# IO_Module.net
KiCad netlist of a schematic drawn in EAGLE
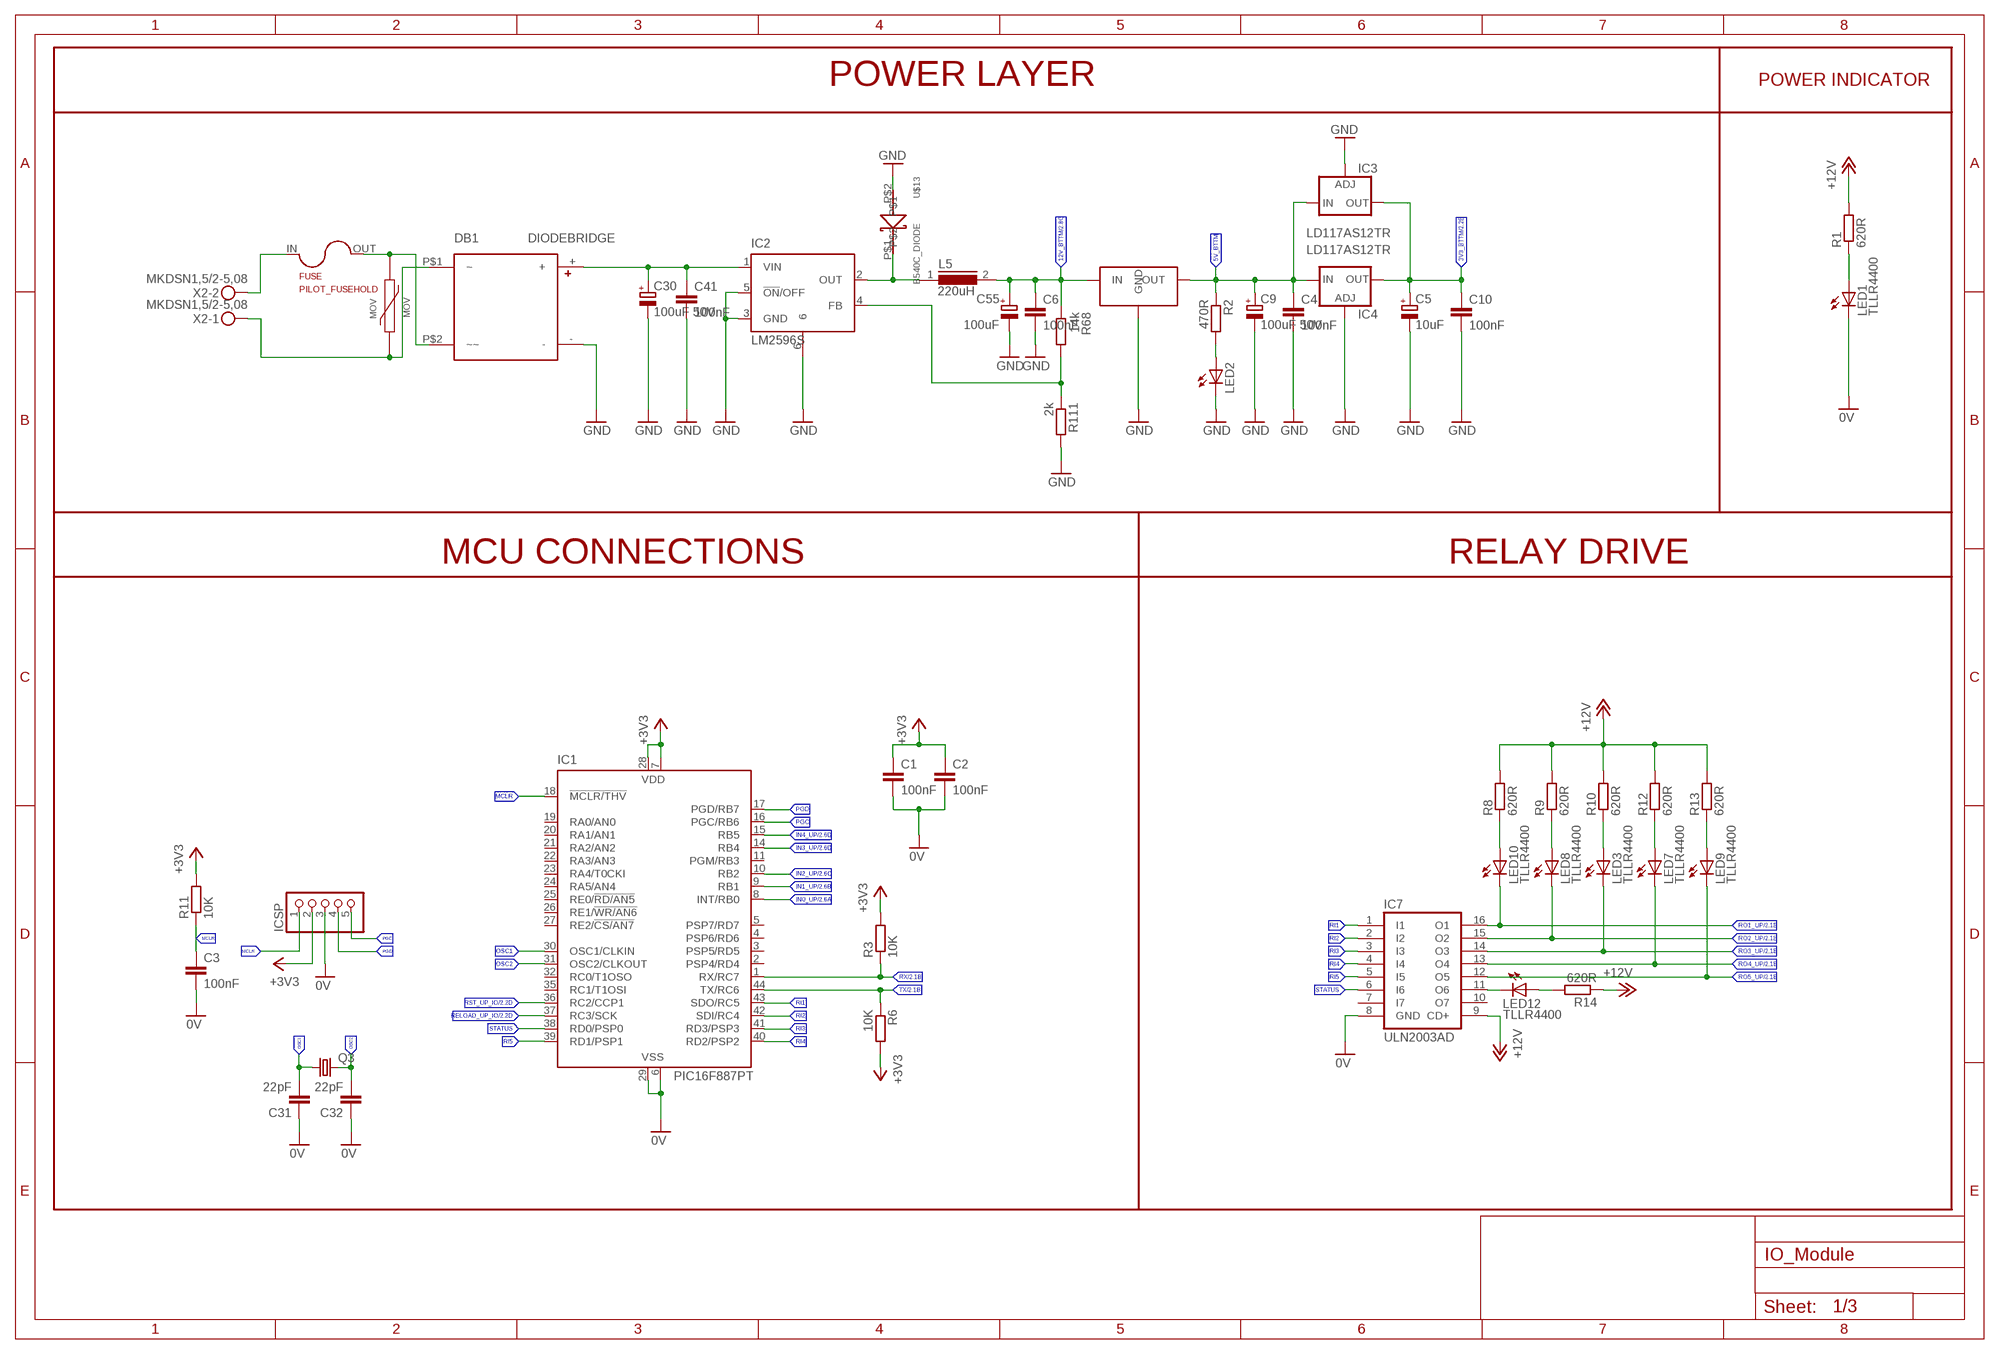
[diagram p0: schematic, sheet 1]
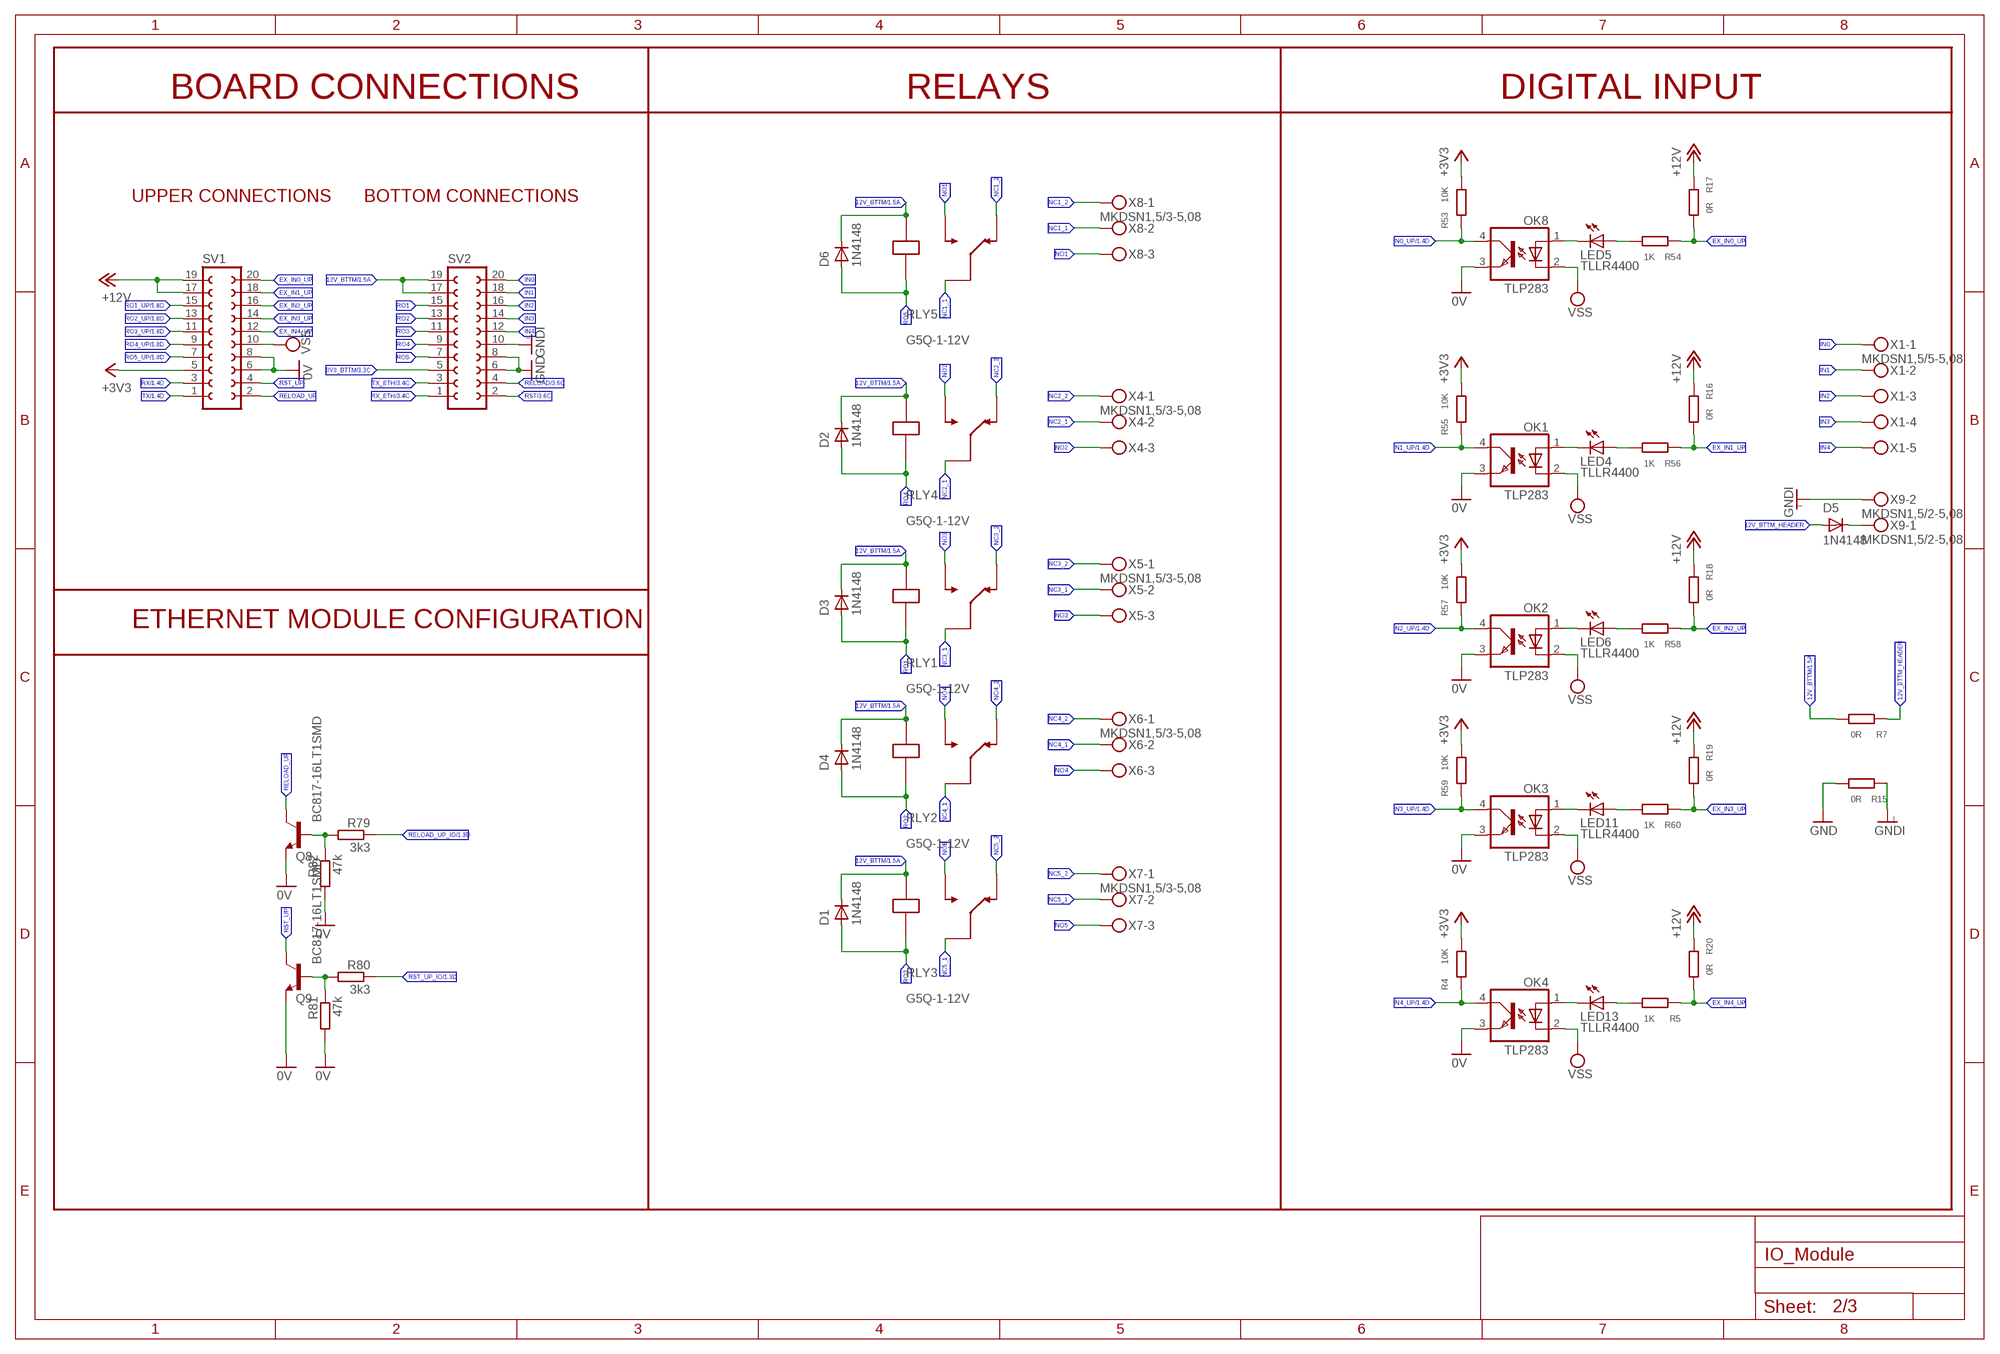
[diagram p1: schematic, sheet 2]
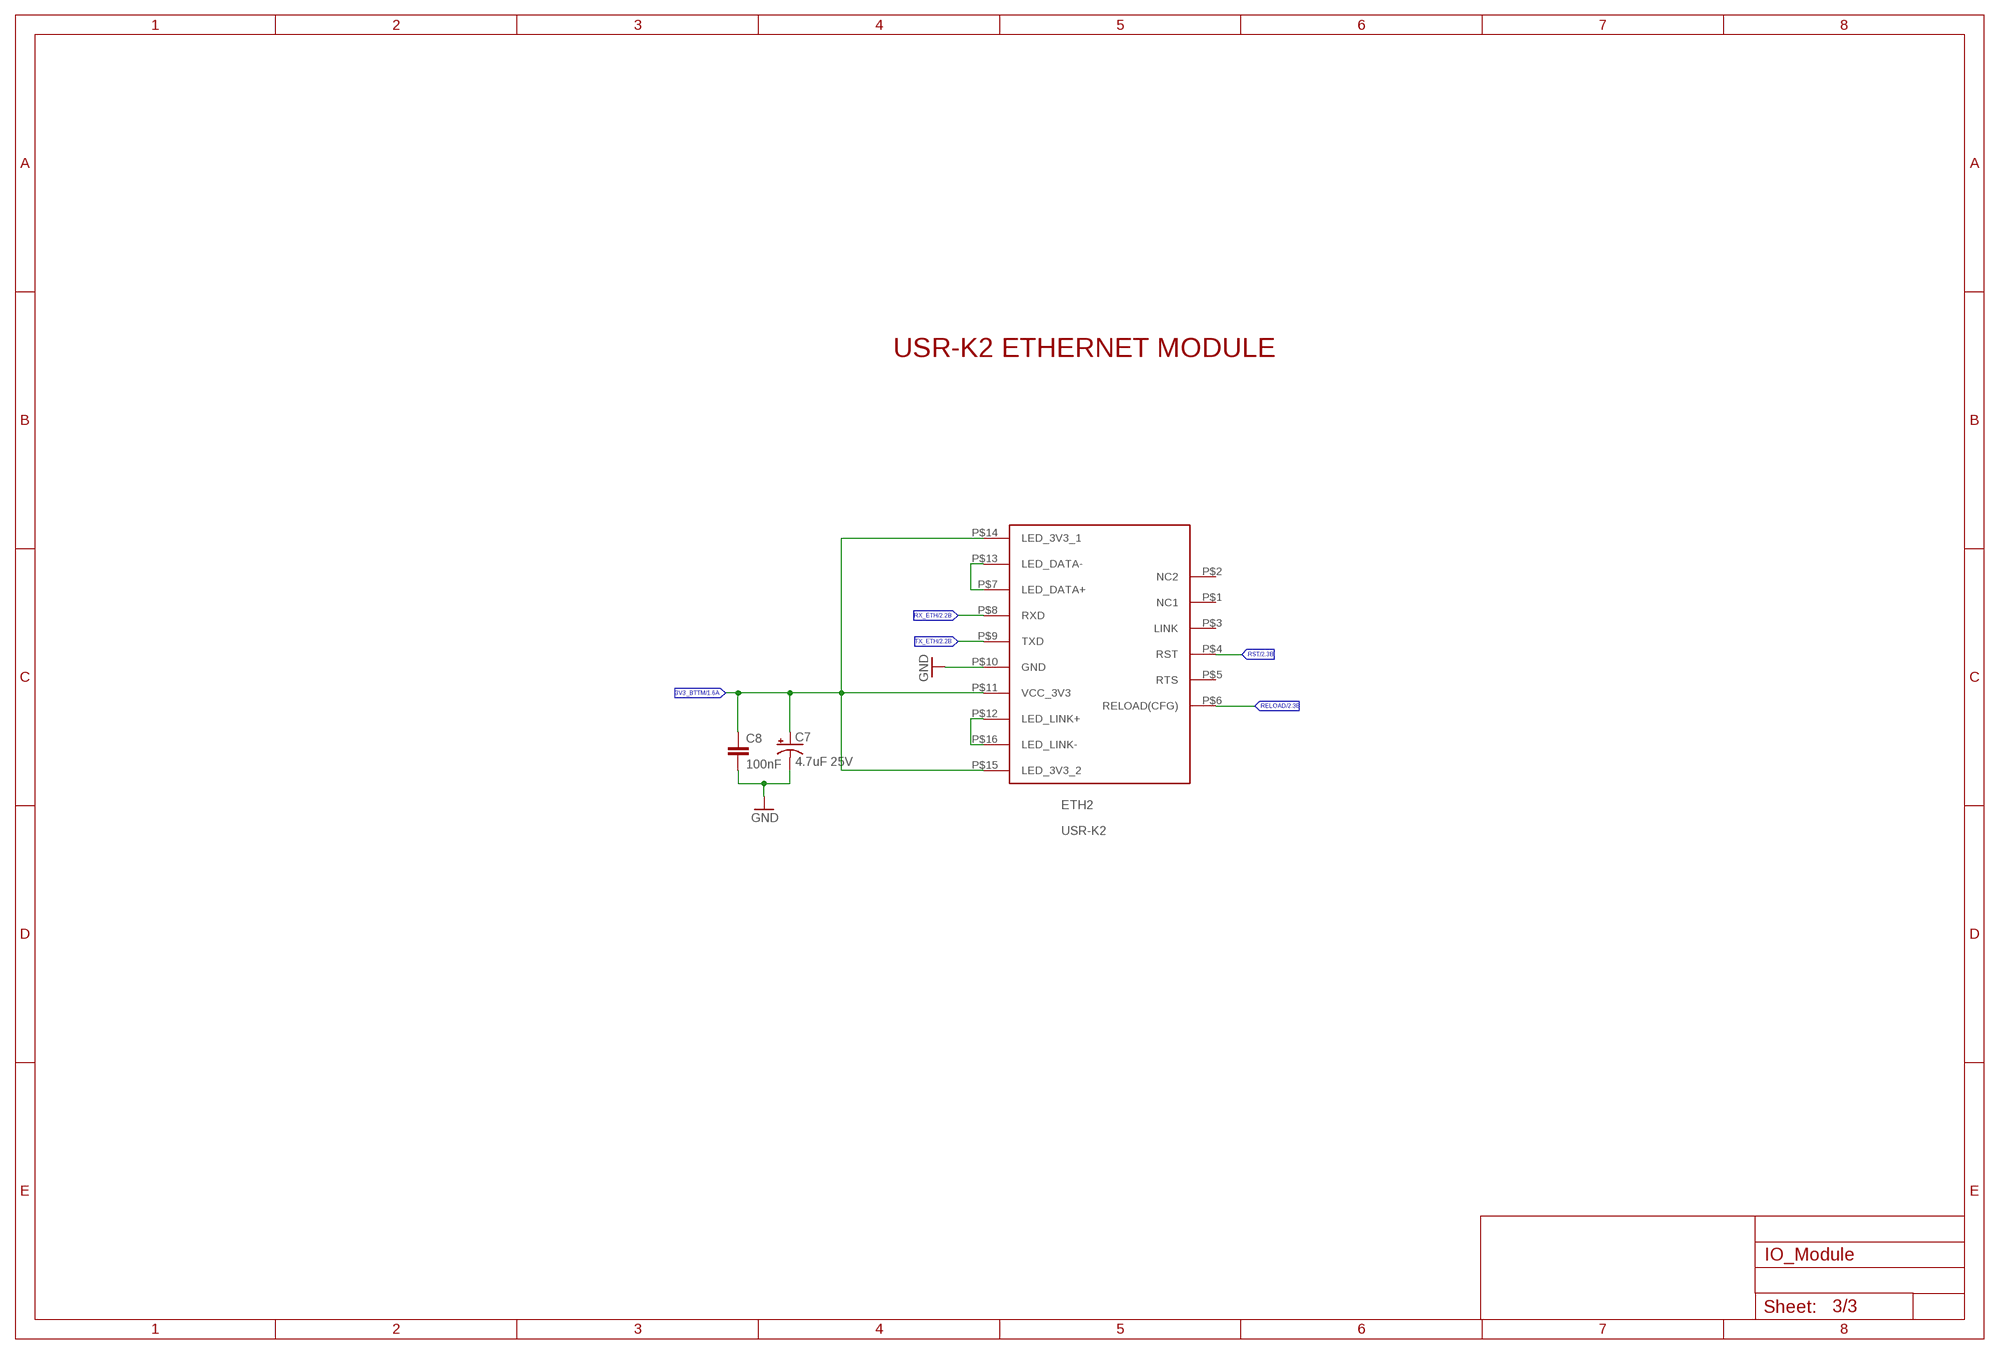
[diagram p2: schematic, sheet 3]

(export (version "E")
  (design (tool "Eeschema 10.0.6"))
  (components
    (comp (ref "C1")
      (value "100nF")
      (footprint "eagle-import:C0603K")
      (libsource (lib "eagle-import") (part "C-EUC0603K"))
    )
    (comp (ref "C2")
      (value "100nF")
      (footprint "eagle-import:C0603K")
      (libsource (lib "eagle-import") (part "C-EUC0603K"))
    )
    (comp (ref "C3")
      (value "100nF")
      (footprint "eagle-import:C0603K")
      (libsource (lib "eagle-import") (part "C-EUC0603K"))
    )
    (comp (ref "C4")
      (value "100nF")
      (footprint "eagle-import:C0603")
      (libsource (lib "eagle-import") (part "C-EUC0603"))
    )
    (comp (ref "C5")
      (value "10uF")
      (footprint "eagle-import:153CLV-0505")
      (libsource (lib "eagle-import") (part "CPOL-EU153CLV-0505"))
    )
    (comp (ref "C6")
      (value "100nF")
      (footprint "eagle-import:C0603")
      (libsource (lib "eagle-import") (part "C-EUC0603"))
    )
    (comp (ref "C9")
      (value "100uF 50V")
      (footprint "eagle-import:153CLV-0810")
      (libsource (lib "eagle-import") (part "CPOL-EU153CLV-0810"))
    )
    (comp (ref "C10")
      (value "100nF")
      (footprint "eagle-import:C0603")
      (libsource (lib "eagle-import") (part "C-EUC0603"))
    )
    (comp (ref "C30")
      (value "100uF 50V")
      (footprint "eagle-import:153CLV-0810")
      (libsource (lib "eagle-import") (part "CPOL-EU153CLV-0810"))
    )
    (comp (ref "C31")
      (value "22pF")
      (footprint "eagle-import:C0805")
      (libsource (lib "eagle-import") (part "C-EUC0805"))
    )
    (comp (ref "C32")
      (value "22pF")
      (footprint "eagle-import:C0805")
      (libsource (lib "eagle-import") (part "C-EUC0805"))
    )
    (comp (ref "C41")
      (value "100nF")
      (footprint "eagle-import:C0603")
      (libsource (lib "eagle-import") (part "C-EUC0603"))
    )
    (comp (ref "C55")
      (value "100uF")
      (footprint "eagle-import:153CLV-0605")
      (libsource (lib "eagle-import") (part "CPOL-EU153CLV-0605"))
    )
    (comp (ref "DB1")
      (value "DIODEBRIDGE")
      (footprint "eagle-import:SDIP")
      (libsource (lib "eagle-import") (part "DIODEBRIDGE"))
    )
    (comp (ref "FUSE")
      (value "PILOT_FUSEHOLD")
      (footprint "eagle-import:RTM_FUSEHOLD")
      (libsource (lib "eagle-import") (part "RTM_FUSEHOLD"))
    )
    (comp (ref "IC1")
      (value "PIC16F887PT")
      (footprint "eagle-import:TQFP44")
      (fields (field (name "MF") "MICROCHIP") (field (name "MPN") "PIC16F877-04/PQ"))
      (libsource (lib "eagle-import") (part "PIC16F87PT7"))
    )
    (comp (ref "IC2")
      (value "LM2596S")
      (footprint "eagle-import:TO263-5")
      (fields (field (name "MF") "NATIONAL SEMICONDUCTOR") (field (name "MPN") "LM2596S-ADJ/NOPB"))
      (libsource (lib "eagle-import") (part "LM2596S"))
    )
    (comp (ref "IC3")
      (value "LD117AS12TR")
      (footprint "eagle-import:SOT223")
      (libsource (lib "eagle-import") (part "LD117A?S12TR"))
    )
    (comp (ref "IC4")
      (value "LD117AS12TR")
      (footprint "eagle-import:SOT223")
      (libsource (lib "eagle-import") (part "LD117A?S12TR"))
    )
    (comp (ref "IC7")
      (value "ULN2003AD")
      (footprint "eagle-import:SO16")
      (libsource (lib "eagle-import") (part "ULN2003AD"))
    )
    (comp (ref "ICSP")
      (value "PINHD-1X5")
      (footprint "eagle-import:1X05")
      (libsource (lib "eagle-import") (part "PINHD-1X5"))
    )
    (comp (ref "L5")
      (value "220uH")
      (footprint "eagle-import:DR125")
      (libsource (lib "eagle-import") (part "DR125"))
    )
    (comp (ref "LED1")
      (value "TLLR4400")
      (footprint "eagle-import:LED3MM")
      (fields (field (name "MF") "VISHAY SEMICONDUCTOR"))
      (libsource (lib "eagle-import") (part "TLLR4400"))
    )
    (comp (ref "LED2")
      (value "LEDCHIPLED_0805")
      (footprint "eagle-import:CHIPLED_0805")
      (libsource (lib "eagle-import") (part "LEDCHIPLED_0805"))
    )
    (comp (ref "LED3")
      (value "TLLR4400")
      (footprint "eagle-import:LED3MM")
      (fields (field (name "MF") "VISHAY SEMICONDUCTOR"))
      (libsource (lib "eagle-import") (part "TLLR4400"))
    )
    (comp (ref "LED7")
      (value "TLLR4400")
      (footprint "eagle-import:LED3MM")
      (fields (field (name "MF") "VISHAY SEMICONDUCTOR"))
      (libsource (lib "eagle-import") (part "TLLR4400"))
    )
    (comp (ref "LED8")
      (value "TLLR4400")
      (footprint "eagle-import:LED3MM")
      (fields (field (name "MF") "VISHAY SEMICONDUCTOR"))
      (libsource (lib "eagle-import") (part "TLLR4400"))
    )
    (comp (ref "LED9")
      (value "TLLR4400")
      (footprint "eagle-import:LED3MM")
      (fields (field (name "MF") "VISHAY SEMICONDUCTOR"))
      (libsource (lib "eagle-import") (part "TLLR4400"))
    )
    (comp (ref "LED10")
      (value "TLLR4400")
      (footprint "eagle-import:LED3MM")
      (fields (field (name "MF") "VISHAY SEMICONDUCTOR"))
      (libsource (lib "eagle-import") (part "TLLR4400"))
    )
    (comp (ref "LED12")
      (value "TLLR4400")
      (footprint "eagle-import:LED3MM")
      (fields (field (name "MF") "VISHAY SEMICONDUCTOR"))
      (libsource (lib "eagle-import") (part "TLLR4400"))
    )
    (comp (ref "MOV")
      (value "MOV-10D201K")
      (footprint "eagle-import:MOV-10D201K")
      (libsource (lib "eagle-import") (part "MOV-10D201K"))
    )
    (comp (ref "Q3")
      (value "CRYSTALHC49UP")
      (footprint "eagle-import:HC49UP")
      (libsource (lib "eagle-import") (part "CRYSTALHC49UP"))
    )
    (comp (ref "R1")
      (value "620R")
      (footprint "eagle-import:R0805")
      (libsource (lib "eagle-import") (part "R-EU_R0805"))
    )
    (comp (ref "R2")
      (value "470R")
      (footprint "eagle-import:R0805")
      (libsource (lib "eagle-import") (part "R-EU_R0805"))
    )
    (comp (ref "R3")
      (value "10K")
      (footprint "eagle-import:R0805")
      (libsource (lib "eagle-import") (part "R-EU_R0805"))
    )
    (comp (ref "R6")
      (value "10K")
      (footprint "eagle-import:R0805")
      (libsource (lib "eagle-import") (part "R-EU_R0805"))
    )
    (comp (ref "R8")
      (value "620R")
      (footprint "eagle-import:R0805")
      (libsource (lib "eagle-import") (part "R-EU_R0805"))
    )
    (comp (ref "R9")
      (value "620R")
      (footprint "eagle-import:R0805")
      (libsource (lib "eagle-import") (part "R-EU_R0805"))
    )
    (comp (ref "R10")
      (value "620R")
      (footprint "eagle-import:R0805")
      (libsource (lib "eagle-import") (part "R-EU_R0805"))
    )
    (comp (ref "R11")
      (value "10K")
      (footprint "eagle-import:R0805")
      (libsource (lib "eagle-import") (part "R-EU_R0805"))
    )
    (comp (ref "R12")
      (value "620R")
      (footprint "eagle-import:R0805")
      (libsource (lib "eagle-import") (part "R-EU_R0805"))
    )
    (comp (ref "R13")
      (value "620R")
      (footprint "eagle-import:R0805")
      (libsource (lib "eagle-import") (part "R-EU_R0805"))
    )
    (comp (ref "R14")
      (value "620R")
      (footprint "eagle-import:R0805")
      (libsource (lib "eagle-import") (part "R-EU_R0805"))
    )
    (comp (ref "R68")
      (value "14k")
      (footprint "eagle-import:M0805")
      (libsource (lib "eagle-import") (part "R-EU_M0805"))
    )
    (comp (ref "R111")
      (value "2k")
      (footprint "eagle-import:M0805")
      (libsource (lib "eagle-import") (part "R-EU_M0805"))
    )
    (comp (ref "U$6")
      (value "L7805CD2T-TR")
      (footprint "eagle-import:VREG-7805-DPAK2")
      (libsource (lib "eagle-import") (part "VREG-7805-DPAK2"))
    )
    (comp (ref "U$13")
      (value "B540C_DIODE")
      (footprint "eagle-import:SMC")
      (libsource (lib "eagle-import") (part "B540C_DIODE"))
    )
    (comp (ref "X2")
      (value "MKDSN1,5/2-5,08")
      (footprint "eagle-import:MKDSN1,5_2-5,08")
      (libsource (lib "eagle-import") (part "MKDSN1,5/2-5,08"))
    )
    (comp (ref "C7")
      (value "4.7uF 25V")
      (footprint "eagle-import:A_3216-18R")
      (libsource (lib "eagle-import") (part "CPOL-USA/3216-18R"))
    )
    (comp (ref "C8")
      (value "100nF")
      (footprint "eagle-import:C0603")
      (libsource (lib "eagle-import") (part "C-EUC0603"))
    )
    (comp (ref "ETH2")
      (value "USR-K2")
      (footprint "eagle-import:USR-K2")
      (libsource (lib "eagle-import") (part "USR-K2"))
    )
    (comp (ref "D1")
      (value "1N4148")
      (footprint "eagle-import:SMA-DO214AC")
      (libsource (lib "eagle-import") (part "GF1"))
    )
    (comp (ref "D2")
      (value "1N4148")
      (footprint "eagle-import:SMA-DO214AC")
      (libsource (lib "eagle-import") (part "GF1"))
    )
    (comp (ref "D3")
      (value "1N4148")
      (footprint "eagle-import:SMA-DO214AC")
      (libsource (lib "eagle-import") (part "GF1"))
    )
    (comp (ref "D4")
      (value "1N4148")
      (footprint "eagle-import:SMA-DO214AC")
      (libsource (lib "eagle-import") (part "GF1"))
    )
    (comp (ref "D5")
      (value "1N4148")
      (footprint "eagle-import:SMA-DO214AC")
      (libsource (lib "eagle-import") (part "GF1"))
    )
    (comp (ref "D6")
      (value "1N4148")
      (footprint "eagle-import:SMA-DO214AC")
      (libsource (lib "eagle-import") (part "GF1"))
    )
    (comp (ref "LED4")
      (value "TLLR4400")
      (footprint "eagle-import:LED3MM")
      (fields (field (name "MF") "VISHAY SEMICONDUCTOR"))
      (libsource (lib "eagle-import") (part "TLLR4400"))
    )
    (comp (ref "LED5")
      (value "TLLR4400")
      (footprint "eagle-import:LED3MM")
      (fields (field (name "MF") "VISHAY SEMICONDUCTOR"))
      (libsource (lib "eagle-import") (part "TLLR4400"))
    )
    (comp (ref "LED6")
      (value "TLLR4400")
      (footprint "eagle-import:LED3MM")
      (fields (field (name "MF") "VISHAY SEMICONDUCTOR"))
      (libsource (lib "eagle-import") (part "TLLR4400"))
    )
    (comp (ref "LED11")
      (value "TLLR4400")
      (footprint "eagle-import:LED3MM")
      (fields (field (name "MF") "VISHAY SEMICONDUCTOR"))
      (libsource (lib "eagle-import") (part "TLLR4400"))
    )
    (comp (ref "LED13")
      (value "TLLR4400")
      (footprint "eagle-import:LED3MM")
      (fields (field (name "MF") "VISHAY SEMICONDUCTOR"))
      (libsource (lib "eagle-import") (part "TLLR4400"))
    )
    (comp (ref "OK1")
      (value "TLP283")
      (footprint "eagle-import:MINI-FLAT-4")
      (libsource (lib "eagle-import") (part "TLP283"))
    )
    (comp (ref "OK2")
      (value "TLP283")
      (footprint "eagle-import:MINI-FLAT-4")
      (libsource (lib "eagle-import") (part "TLP283"))
    )
    (comp (ref "OK3")
      (value "TLP283")
      (footprint "eagle-import:MINI-FLAT-4")
      (libsource (lib "eagle-import") (part "TLP283"))
    )
    (comp (ref "OK4")
      (value "TLP283")
      (footprint "eagle-import:MINI-FLAT-4")
      (libsource (lib "eagle-import") (part "TLP283"))
    )
    (comp (ref "OK8")
      (value "TLP283")
      (footprint "eagle-import:MINI-FLAT-4")
      (libsource (lib "eagle-import") (part "TLP283"))
    )
    (comp (ref "Q8")
      (value "BC817-16LT1SMD")
      (footprint "eagle-import:SOT23-BEC")
      (libsource (lib "eagle-import") (part "BC817SMD-16LT1"))
    )
    (comp (ref "Q9")
      (value "BC817-16LT1SMD")
      (footprint "eagle-import:SOT23-BEC")
      (libsource (lib "eagle-import") (part "BC817SMD-16LT1"))
    )
    (comp (ref "R4")
      (value "10K")
      (footprint "eagle-import:M0805")
      (libsource (lib "eagle-import") (part "R-EU_M0805"))
    )
    (comp (ref "R5")
      (value "1K")
      (footprint "eagle-import:M0805")
      (libsource (lib "eagle-import") (part "R-EU_M0805"))
    )
    (comp (ref "R7")
      (value "0R")
      (footprint "eagle-import:M0805")
      (libsource (lib "eagle-import") (part "R-EU_M0805"))
    )
    (comp (ref "R15")
      (value "0R")
      (footprint "eagle-import:M0805")
      (libsource (lib "eagle-import") (part "R-EU_M0805"))
    )
    (comp (ref "R16")
      (value "0R")
      (footprint "eagle-import:M0805")
      (libsource (lib "eagle-import") (part "R-EU_M0805"))
    )
    (comp (ref "R17")
      (value "0R")
      (footprint "eagle-import:M0805")
      (libsource (lib "eagle-import") (part "R-EU_M0805"))
    )
    (comp (ref "R18")
      (value "0R")
      (footprint "eagle-import:M0805")
      (libsource (lib "eagle-import") (part "R-EU_M0805"))
    )
    (comp (ref "R19")
      (value "0R")
      (footprint "eagle-import:M0805")
      (libsource (lib "eagle-import") (part "R-EU_M0805"))
    )
    (comp (ref "R20")
      (value "0R")
      (footprint "eagle-import:M0805")
      (libsource (lib "eagle-import") (part "R-EU_M0805"))
    )
    (comp (ref "R53")
      (value "10K")
      (footprint "eagle-import:M0805")
      (libsource (lib "eagle-import") (part "R-EU_M0805"))
    )
    (comp (ref "R54")
      (value "1K")
      (footprint "eagle-import:M0805")
      (libsource (lib "eagle-import") (part "R-EU_M0805"))
    )
    (comp (ref "R55")
      (value "10K")
      (footprint "eagle-import:M0805")
      (libsource (lib "eagle-import") (part "R-EU_M0805"))
    )
    (comp (ref "R56")
      (value "1K")
      (footprint "eagle-import:M0805")
      (libsource (lib "eagle-import") (part "R-EU_M0805"))
    )
    (comp (ref "R57")
      (value "10K")
      (footprint "eagle-import:M0805")
      (libsource (lib "eagle-import") (part "R-EU_M0805"))
    )
    (comp (ref "R58")
      (value "1K")
      (footprint "eagle-import:M0805")
      (libsource (lib "eagle-import") (part "R-EU_M0805"))
    )
    (comp (ref "R59")
      (value "10K")
      (footprint "eagle-import:M0805")
      (libsource (lib "eagle-import") (part "R-EU_M0805"))
    )
    (comp (ref "R60")
      (value "1K")
      (footprint "eagle-import:M0805")
      (libsource (lib "eagle-import") (part "R-EU_M0805"))
    )
    (comp (ref "R79")
      (value "3k3")
      (footprint "eagle-import:R0805")
      (libsource (lib "eagle-import") (part "R-EU_R0805"))
    )
    (comp (ref "R80")
      (value "3k3")
      (footprint "eagle-import:R0805")
      (libsource (lib "eagle-import") (part "R-EU_R0805"))
    )
    (comp (ref "R81")
      (value "47k")
      (footprint "eagle-import:R0805")
      (libsource (lib "eagle-import") (part "R-EU_R0805"))
    )
    (comp (ref "R82")
      (value "47k")
      (footprint "eagle-import:R0805")
      (libsource (lib "eagle-import") (part "R-EU_R0805"))
    )
    (comp (ref "RLY1")
      (value "JW1FSN-DC12V")
      (footprint "eagle-import:G5Q-1-12V")
      (libsource (lib "eagle-import") (part "G5Q-1-12V"))
    )
    (comp (ref "RLY2")
      (value "JW1FSN-DC12V")
      (footprint "eagle-import:G5Q-1-12V")
      (libsource (lib "eagle-import") (part "G5Q-1-12V"))
    )
    (comp (ref "RLY3")
      (value "JW1FSN-DC12V")
      (footprint "eagle-import:G5Q-1-12V")
      (libsource (lib "eagle-import") (part "G5Q-1-12V"))
    )
    (comp (ref "RLY4")
      (value "JW1FSN-DC12V")
      (footprint "eagle-import:G5Q-1-12V")
      (libsource (lib "eagle-import") (part "G5Q-1-12V"))
    )
    (comp (ref "RLY5")
      (value "JW1FSN-DC12V")
      (footprint "eagle-import:G5Q-1-12V")
      (libsource (lib "eagle-import") (part "G5Q-1-12V"))
    )
    (comp (ref "SV1")
      (value "FE10-2")
      (footprint "eagle-import:FE10-2")
      (libsource (lib "eagle-import") (part "FE10-2"))
    )
    (comp (ref "SV2")
      (value "FE10-2")
      (footprint "eagle-import:FE10-2")
      (libsource (lib "eagle-import") (part "FE10-2"))
    )
    (comp (ref "X1")
      (value "MKDSN1,5/5-5,08")
      (footprint "eagle-import:MKDSN1,5_5-5,08")
      (libsource (lib "eagle-import") (part "MKDSN1,5/5-5,08"))
    )
    (comp (ref "X4")
      (value "MKDSN1,5/3-5,08")
      (footprint "eagle-import:MKDSN1,5_3-5,08")
      (libsource (lib "eagle-import") (part "MKDSN1,5/3-5,08"))
    )
    (comp (ref "X5")
      (value "MKDSN1,5/3-5,08")
      (footprint "eagle-import:MKDSN1,5_3-5,08")
      (libsource (lib "eagle-import") (part "MKDSN1,5/3-5,08"))
    )
    (comp (ref "X6")
      (value "MKDSN1,5/3-5,08")
      (footprint "eagle-import:MKDSN1,5_3-5,08")
      (libsource (lib "eagle-import") (part "MKDSN1,5/3-5,08"))
    )
    (comp (ref "X7")
      (value "MKDSN1,5/3-5,08")
      (footprint "eagle-import:MKDSN1,5_3-5,08")
      (libsource (lib "eagle-import") (part "MKDSN1,5/3-5,08"))
    )
    (comp (ref "X8")
      (value "MKDSN1,5/3-5,08")
      (footprint "eagle-import:MKDSN1,5_3-5,08")
      (libsource (lib "eagle-import") (part "MKDSN1,5/3-5,08"))
    )
    (comp (ref "X9")
      (value "MKDSN1,5/2-5,08")
      (footprint "eagle-import:MKDSN1,5_2-5,08")
      (libsource (lib "eagle-import") (part "MKDSN1,5/2-5,08"))
    )
  )
  (nets
    (net (code "1") (name "+3V3") (class "Default")
      (node (ref "C1") (pin "1") (pinfunction "1_1") (pintype "passive"))
      (node (ref "C2") (pin "1") (pinfunction "1_1") (pintype "passive"))
      (node (ref "IC1") (pin "28") (pinfunction "VDD_28") (pintype "power_in"))
      (node (ref "IC1") (pin "7") (pinfunction "VDD_7") (pintype "power_in"))
      (node (ref "ICSP") (pin "2") (pinfunction "2_2") (pintype "passive"))
      (node (ref "R11") (pin "2") (pinfunction "2_2") (pintype "passive"))
      (node (ref "R3") (pin "2") (pinfunction "2_2") (pintype "passive"))
      (node (ref "R4") (pin "2") (pinfunction "2_2") (pintype "passive"))
      (node (ref "R53") (pin "2") (pinfunction "2_2") (pintype "passive"))
      (node (ref "R55") (pin "2") (pinfunction "2_2") (pintype "passive"))
      (node (ref "R57") (pin "2") (pinfunction "2_2") (pintype "passive"))
      (node (ref "R59") (pin "2") (pinfunction "2_2") (pintype "passive"))
      (node (ref "R6") (pin "2") (pinfunction "2_2") (pintype "passive"))
      (node (ref "SV1") (pin "5") (pinfunction "5_5") (pintype "passive"))
    )
    (net (code "2") (name "+12V") (class "Default")
      (node (ref "IC7") (pin "9") (pinfunction "CD+_9") (pintype "passive"))
      (node (ref "R1") (pin "2") (pinfunction "2_2") (pintype "passive"))
      (node (ref "R10") (pin "2") (pinfunction "2_2") (pintype "passive"))
      (node (ref "R12") (pin "2") (pinfunction "2_2") (pintype "passive"))
      (node (ref "R13") (pin "2") (pinfunction "2_2") (pintype "passive"))
      (node (ref "R14") (pin "1") (pinfunction "1_1") (pintype "passive"))
      (node (ref "R16") (pin "1") (pinfunction "1_1") (pintype "passive"))
      (node (ref "R17") (pin "1") (pinfunction "1_1") (pintype "passive"))
      (node (ref "R18") (pin "1") (pinfunction "1_1") (pintype "passive"))
      (node (ref "R19") (pin "1") (pinfunction "1_1") (pintype "passive"))
      (node (ref "R20") (pin "1") (pinfunction "1_1") (pintype "passive"))
      (node (ref "R8") (pin "2") (pinfunction "2_2") (pintype "passive"))
      (node (ref "R9") (pin "2") (pinfunction "2_2") (pintype "passive"))
      (node (ref "SV1") (pin "17") (pinfunction "17_17") (pintype "passive"))
      (node (ref "SV1") (pin "19") (pinfunction "19_19") (pintype "passive"))
    )
    (net (code "3") (name "0V") (class "Default")
      (node (ref "C1") (pin "2") (pinfunction "2_2") (pintype "passive"))
      (node (ref "C2") (pin "2") (pinfunction "2_2") (pintype "passive"))
      (node (ref "C3") (pin "2") (pinfunction "2_2") (pintype "passive"))
      (node (ref "C31") (pin "1") (pinfunction "1_1") (pintype "passive"))
      (node (ref "C32") (pin "1") (pinfunction "1_1") (pintype "passive"))
      (node (ref "IC1") (pin "29") (pinfunction "VSS_29") (pintype "power_in"))
      (node (ref "IC1") (pin "6") (pinfunction "VSS_6") (pintype "power_in"))
      (node (ref "IC7") (pin "8") (pinfunction "GND_8") (pintype "power_in"))
      (node (ref "ICSP") (pin "3") (pinfunction "3_3") (pintype "passive"))
      (node (ref "LED1") (pin "K") (pinfunction "C_K") (pintype "passive"))
      (node (ref "OK1") (pin "3") (pinfunction "EMIT_3") (pintype "passive"))
      (node (ref "OK2") (pin "3") (pinfunction "EMIT_3") (pintype "passive"))
      (node (ref "OK3") (pin "3") (pinfunction "EMIT_3") (pintype "passive"))
      (node (ref "OK4") (pin "3") (pinfunction "EMIT_3") (pintype "passive"))
      (node (ref "OK8") (pin "3") (pinfunction "EMIT_3") (pintype "passive"))
      (node (ref "Q8") (pin "E") (pinfunction "E_E") (pintype "passive"))
      (node (ref "Q9") (pin "E") (pinfunction "E_E") (pintype "passive"))
      (node (ref "R81") (pin "2") (pinfunction "2_2") (pintype "passive"))
      (node (ref "R82") (pin "2") (pinfunction "2_2") (pintype "passive"))
      (node (ref "SV1") (pin "6") (pinfunction "6_6") (pintype "passive"))
      (node (ref "SV1") (pin "8") (pinfunction "8_8") (pintype "passive"))
    )
    (net (code "4") (name "3V3_BTTM") (class "Default")
      (node (ref "C10") (pin "1") (pinfunction "1_1") (pintype "passive"))
      (node (ref "C5") (pin "+") (pinfunction "+_+") (pintype "passive"))
      (node (ref "C7") (pin "+") (pinfunction "+_+") (pintype "passive"))
      (node (ref "C8") (pin "1") (pinfunction "1_1") (pintype "passive"))
      (node (ref "ETH2") (pin "P$11") (pinfunction "VCC_3V3_P$11") (pintype "bidirectional"))
      (node (ref "ETH2") (pin "P$14") (pinfunction "LED_3V3_1_P$14") (pintype "bidirectional"))
      (node (ref "ETH2") (pin "P$15") (pinfunction "LED_3V3_2_P$15") (pintype "bidirectional"))
      (node (ref "IC3") (pin "4") (pinfunction "OUT_4") (pintype "passive"))
      (node (ref "IC4") (pin "4") (pinfunction "OUT_4") (pintype "passive"))
      (node (ref "SV2") (pin "5") (pinfunction "5_5") (pintype "passive"))
    )
    (net (code "5") (name "5V_BTTM") (class "Default")
      (node (ref "C4") (pin "1") (pinfunction "1_1") (pintype "passive"))
      (node (ref "C9") (pin "+") (pinfunction "+_+") (pintype "passive"))
      (node (ref "IC3") (pin "3") (pinfunction "IN_3") (pintype "input"))
      (node (ref "IC4") (pin "3") (pinfunction "IN_3") (pintype "input"))
      (node (ref "R2") (pin "1") (pinfunction "1_1") (pintype "passive"))
      (node (ref "U$6") (pin "VOUT") (pinfunction "OUT_VOUT") (pintype "bidirectional"))
    )
    (net (code "6") (name "12V_BTTM") (class "Default")
      (node (ref "C55") (pin "+") (pinfunction "+_+") (pintype "passive"))
      (node (ref "C6") (pin "1") (pinfunction "1_1") (pintype "passive"))
      (node (ref "D1") (pin "K") (pinfunction "C_K") (pintype "passive"))
      (node (ref "D2") (pin "K") (pinfunction "C_K") (pintype "passive"))
      (node (ref "D3") (pin "K") (pinfunction "C_K") (pintype "passive"))
      (node (ref "D4") (pin "K") (pinfunction "C_K") (pintype "passive"))
      (node (ref "D6") (pin "K") (pinfunction "C_K") (pintype "passive"))
      (node (ref "L5") (pin "2") (pinfunction "2_2") (pintype "passive"))
      (node (ref "R68") (pin "1") (pinfunction "1_1") (pintype "passive"))
      (node (ref "R7") (pin "2") (pinfunction "2_2") (pintype "passive"))
      (node (ref "RLY1") (pin "1") (pinfunction "1_1") (pintype "bidirectional"))
      (node (ref "RLY2") (pin "1") (pinfunction "1_1") (pintype "bidirectional"))
      (node (ref "RLY3") (pin "1") (pinfunction "1_1") (pintype "bidirectional"))
      (node (ref "RLY4") (pin "1") (pinfunction "1_1") (pintype "bidirectional"))
      (node (ref "RLY5") (pin "1") (pinfunction "1_1") (pintype "bidirectional"))
      (node (ref "SV2") (pin "17") (pinfunction "17_17") (pintype "passive"))
      (node (ref "SV2") (pin "19") (pinfunction "19_19") (pintype "passive"))
      (node (ref "U$6") (pin "VIN") (pinfunction "IN_VIN") (pintype "bidirectional"))
    )
    (net (code "7") (name "12V_BTTM_HEADER") (class "Default")
      (node (ref "D5") (pin "A") (pinfunction "A_A") (pintype "passive"))
      (node (ref "R7") (pin "1") (pinfunction "1_1") (pintype "passive"))
    )
    (net (code "8") (name "EX_IN0_UP") (class "Default")
      (node (ref "R17") (pin "2") (pinfunction "2_2") (pintype "passive"))
      (node (ref "R54") (pin "1") (pinfunction "1_1") (pintype "passive"))
      (node (ref "SV1") (pin "20") (pinfunction "20_20") (pintype "passive"))
    )
    (net (code "9") (name "EX_IN1_UP") (class "Default")
      (node (ref "R16") (pin "2") (pinfunction "2_2") (pintype "passive"))
      (node (ref "R56") (pin "1") (pinfunction "1_1") (pintype "passive"))
      (node (ref "SV1") (pin "18") (pinfunction "18_18") (pintype "passive"))
    )
    (net (code "10") (name "EX_IN2_UP") (class "Default")
      (node (ref "R18") (pin "2") (pinfunction "2_2") (pintype "passive"))
      (node (ref "R58") (pin "1") (pinfunction "1_1") (pintype "passive"))
      (node (ref "SV1") (pin "16") (pinfunction "16_16") (pintype "passive"))
    )
    (net (code "11") (name "EX_IN3_UP") (class "Default")
      (node (ref "R19") (pin "2") (pinfunction "2_2") (pintype "passive"))
      (node (ref "R60") (pin "1") (pinfunction "1_1") (pintype "passive"))
      (node (ref "SV1") (pin "14") (pinfunction "14_14") (pintype "passive"))
    )
    (net (code "12") (name "EX_IN4_UP") (class "Default")
      (node (ref "R20") (pin "2") (pinfunction "2_2") (pintype "passive"))
      (node (ref "R5") (pin "1") (pinfunction "1_1") (pintype "passive"))
      (node (ref "SV1") (pin "12") (pinfunction "12_12") (pintype "passive"))
    )
    (net (code "13") (name "GND") (class "Default")
      (node (ref "C10") (pin "2") (pinfunction "2_2") (pintype "passive"))
      (node (ref "C30") (pin "-") (pinfunction "-_-") (pintype "passive"))
      (node (ref "C4") (pin "2") (pinfunction "2_2") (pintype "passive"))
      (node (ref "C41") (pin "2") (pinfunction "2_2") (pintype "passive"))
      (node (ref "C5") (pin "-") (pinfunction "-_-") (pintype "passive"))
      (node (ref "C55") (pin "-") (pinfunction "-_-") (pintype "passive"))
      (node (ref "C6") (pin "2") (pinfunction "2_2") (pintype "passive"))
      (node (ref "C7") (pin "-") (pinfunction "-_-") (pintype "passive"))
      (node (ref "C8") (pin "2") (pinfunction "2_2") (pintype "passive"))
      (node (ref "C9") (pin "-") (pinfunction "-_-") (pintype "passive"))
      (node (ref "DB1") (pin "-") (pinfunction "-_-") (pintype "bidirectional"))
      (node (ref "ETH2") (pin "P$10") (pinfunction "GND_P$10") (pintype "bidirectional"))
      (node (ref "IC2") (pin "3") (pinfunction "GND_3") (pintype "power_in"))
      (node (ref "IC2") (pin "5") (pinfunction "~{ON}/OFF_5") (pintype "input"))
      (node (ref "IC2") (pin "6") (pinfunction "6_6") (pintype "bidirectional"))
      (node (ref "IC3") (pin "1") (pinfunction "ADJ_1") (pintype "input"))
      (node (ref "IC4") (pin "1") (pinfunction "ADJ_1") (pintype "input"))
      (node (ref "LED2") (pin "C") (pinfunction "C_C") (pintype "passive"))
      (node (ref "R111") (pin "2") (pinfunction "2_2") (pintype "passive"))
      (node (ref "R15") (pin "2") (pinfunction "2_2") (pintype "passive"))
      (node (ref "SV2") (pin "6") (pinfunction "6_6") (pintype "passive"))
      (node (ref "SV2") (pin "8") (pinfunction "8_8") (pintype "passive"))
      (node (ref "U$13") (pin "P$2") (pinfunction "P$2_P$2") (pintype "bidirectional"))
      (node (ref "U$6") (pin "GND") (pinfunction "GND_GND") (pintype "bidirectional"))
    )
    (net (code "14") (name "GNDI") (class "Default")
      (node (ref "R15") (pin "1") (pinfunction "1_1") (pintype "passive"))
      (node (ref "SV2") (pin "10") (pinfunction "10_10") (pintype "passive"))
      (node (ref "X9") (pin "2") (pinfunction "KL_2") (pintype "passive"))
    )
    (net (code "15") (name "IN0") (class "Default")
      (node (ref "SV2") (pin "20") (pinfunction "20_20") (pintype "passive"))
      (node (ref "X1") (pin "1") (pinfunction "KL_1") (pintype "passive"))
    )
    (net (code "16") (name "IN0_UP") (class "Default")
      (node (ref "IC1") (pin "8") (pinfunction "INT/RB0_8") (pintype "bidirectional"))
      (node (ref "OK8") (pin "4") (pinfunction "COL_4") (pintype "passive"))
      (node (ref "R53") (pin "1") (pinfunction "1_1") (pintype "passive"))
    )
    (net (code "17") (name "IN1") (class "Default")
      (node (ref "SV2") (pin "18") (pinfunction "18_18") (pintype "passive"))
      (node (ref "X1") (pin "2") (pinfunction "KL_2") (pintype "passive"))
    )
    (net (code "18") (name "IN1_UP") (class "Default")
      (node (ref "IC1") (pin "9") (pinfunction "RB1_9") (pintype "bidirectional"))
      (node (ref "OK1") (pin "4") (pinfunction "COL_4") (pintype "passive"))
      (node (ref "R55") (pin "1") (pinfunction "1_1") (pintype "passive"))
    )
    (net (code "19") (name "IN2") (class "Default")
      (node (ref "SV2") (pin "16") (pinfunction "16_16") (pintype "passive"))
      (node (ref "X1") (pin "3") (pinfunction "KL_3") (pintype "passive"))
    )
    (net (code "20") (name "IN2_UP") (class "Default")
      (node (ref "IC1") (pin "10") (pinfunction "RB2_10") (pintype "bidirectional"))
      (node (ref "OK2") (pin "4") (pinfunction "COL_4") (pintype "passive"))
      (node (ref "R57") (pin "1") (pinfunction "1_1") (pintype "passive"))
    )
    (net (code "21") (name "IN3") (class "Default")
      (node (ref "SV2") (pin "14") (pinfunction "14_14") (pintype "passive"))
      (node (ref "X1") (pin "4") (pinfunction "KL_4") (pintype "passive"))
    )
    (net (code "22") (name "IN3_UP") (class "Default")
      (node (ref "IC1") (pin "14") (pinfunction "RB4_14") (pintype "bidirectional"))
      (node (ref "OK3") (pin "4") (pinfunction "COL_4") (pintype "passive"))
      (node (ref "R59") (pin "1") (pinfunction "1_1") (pintype "passive"))
    )
    (net (code "23") (name "IN4") (class "Default")
      (node (ref "SV2") (pin "12") (pinfunction "12_12") (pintype "passive"))
      (node (ref "X1") (pin "5") (pinfunction "KL_5") (pintype "passive"))
    )
    (net (code "24") (name "IN4_UP") (class "Default")
      (node (ref "IC1") (pin "15") (pinfunction "RB5_15") (pintype "bidirectional"))
      (node (ref "OK4") (pin "4") (pinfunction "COL_4") (pintype "passive"))
      (node (ref "R4") (pin "1") (pinfunction "1_1") (pintype "passive"))
    )
    (net (code "25") (name "MCLR") (class "Default")
      (node (ref "C3") (pin "1") (pinfunction "1_1") (pintype "passive"))
      (node (ref "IC1") (pin "18") (pinfunction "~{MCLR/THV}_18") (pintype "input"))
      (node (ref "ICSP") (pin "1") (pinfunction "1_1") (pintype "passive"))
      (node (ref "R11") (pin "1") (pinfunction "1_1") (pintype "passive"))
    )
    (net (code "26") (name "NC1_1") (class "Default")
      (node (ref "RLY5") (pin "3") (pinfunction "3_3") (pintype "bidirectional"))
      (node (ref "X8") (pin "2") (pinfunction "KL_2") (pintype "passive"))
    )
    (net (code "27") (name "NC1_2") (class "Default")
      (node (ref "RLY5") (pin "4") (pinfunction "4_4") (pintype "bidirectional"))
      (node (ref "X8") (pin "1") (pinfunction "KL_1") (pintype "passive"))
    )
    (net (code "28") (name "NC2_1") (class "Default")
      (node (ref "RLY4") (pin "3") (pinfunction "3_3") (pintype "bidirectional"))
      (node (ref "X4") (pin "2") (pinfunction "KL_2") (pintype "passive"))
    )
    (net (code "29") (name "NC2_2") (class "Default")
      (node (ref "RLY4") (pin "4") (pinfunction "4_4") (pintype "bidirectional"))
      (node (ref "X4") (pin "1") (pinfunction "KL_1") (pintype "passive"))
    )
    (net (code "30") (name "NC3_1") (class "Default")
      (node (ref "RLY1") (pin "3") (pinfunction "3_3") (pintype "bidirectional"))
      (node (ref "X5") (pin "2") (pinfunction "KL_2") (pintype "passive"))
    )
    (net (code "31") (name "NC3_2") (class "Default")
      (node (ref "RLY1") (pin "4") (pinfunction "4_4") (pintype "bidirectional"))
      (node (ref "X5") (pin "1") (pinfunction "KL_1") (pintype "passive"))
    )
    (net (code "32") (name "NC4_1") (class "Default")
      (node (ref "RLY2") (pin "3") (pinfunction "3_3") (pintype "bidirectional"))
      (node (ref "X6") (pin "2") (pinfunction "KL_2") (pintype "passive"))
    )
    (net (code "33") (name "NC4_2") (class "Default")
      (node (ref "RLY2") (pin "4") (pinfunction "4_4") (pintype "bidirectional"))
      (node (ref "X6") (pin "1") (pinfunction "KL_1") (pintype "passive"))
    )
    (net (code "34") (name "NC5_1") (class "Default")
      (node (ref "RLY3") (pin "3") (pinfunction "3_3") (pintype "bidirectional"))
      (node (ref "X7") (pin "2") (pinfunction "KL_2") (pintype "passive"))
    )
    (net (code "35") (name "NC5_2") (class "Default")
      (node (ref "RLY3") (pin "4") (pinfunction "4_4") (pintype "bidirectional"))
      (node (ref "X7") (pin "1") (pinfunction "KL_1") (pintype "passive"))
    )
    (net (code "36") (name "NO1") (class "Default")
      (node (ref "RLY5") (pin "5") (pinfunction "5_5") (pintype "bidirectional"))
      (node (ref "X8") (pin "3") (pinfunction "KL_3") (pintype "passive"))
    )
    (net (code "37") (name "NO2") (class "Default")
      (node (ref "RLY4") (pin "5") (pinfunction "5_5") (pintype "bidirectional"))
      (node (ref "X4") (pin "3") (pinfunction "KL_3") (pintype "passive"))
    )
    (net (code "38") (name "NO3") (class "Default")
      (node (ref "RLY1") (pin "5") (pinfunction "5_5") (pintype "bidirectional"))
      (node (ref "X5") (pin "3") (pinfunction "KL_3") (pintype "passive"))
    )
    (net (code "39") (name "NO4") (class "Default")
      (node (ref "RLY2") (pin "5") (pinfunction "5_5") (pintype "bidirectional"))
      (node (ref "X6") (pin "3") (pinfunction "KL_3") (pintype "passive"))
    )
    (net (code "40") (name "NO5") (class "Default")
      (node (ref "RLY3") (pin "5") (pinfunction "5_5") (pintype "bidirectional"))
      (node (ref "X7") (pin "3") (pinfunction "KL_3") (pintype "passive"))
    )
    (net (code "41") (name "Net-(D5-C)") (class "Default")
      (node (ref "D5") (pin "K") (pinfunction "C_K") (pintype "passive"))
      (node (ref "X9") (pin "1") (pinfunction "KL_1") (pintype "passive"))
    )
    (net (code "42") (name "Net-(DB1-~-PadP$2)") (class "Default")
      (node (ref "DB1") (pin "P$2") (pinfunction "~_P$2") (pintype "bidirectional"))
      (node (ref "FUSE") (pin "OUT") (pinfunction "OUT_OUT") (pintype "bidirectional"))
      (node (ref "MOV") (pin "2") (pinfunction "2_2") (pintype "bidirectional"))
    )
    (net (code "43") (name "Net-(ETH2-LED_DATA+)") (class "Default")
      (node (ref "ETH2") (pin "P$13") (pinfunction "LED_DATA-_P$13") (pintype "bidirectional"))
      (node (ref "ETH2") (pin "P$7") (pinfunction "LED_DATA+_P$7") (pintype "bidirectional"))
    )
    (net (code "44") (name "Net-(ETH2-LED_LINK+)") (class "Default")
      (node (ref "ETH2") (pin "P$12") (pinfunction "LED_LINK+_P$12") (pintype "bidirectional"))
      (node (ref "ETH2") (pin "P$16") (pinfunction "LED_LINK-_P$16") (pintype "bidirectional"))
    )
    (net (code "45") (name "Net-(IC2-FB)") (class "Default")
      (node (ref "IC2") (pin "4") (pinfunction "FB_4") (pintype "input"))
      (node (ref "R111") (pin "1") (pinfunction "1_1") (pintype "passive"))
      (node (ref "R68") (pin "2") (pinfunction "2_2") (pintype "passive"))
    )
    (net (code "46") (name "Net-(IC2-OUT)") (class "Default")
      (node (ref "IC2") (pin "2") (pinfunction "OUT_2") (pintype "output"))
      (node (ref "L5") (pin "1") (pinfunction "1_1") (pintype "passive"))
      (node (ref "U$13") (pin "P$1") (pinfunction "P$1_P$1") (pintype "bidirectional"))
    )
    (net (code "47") (name "Net-(IC2-VIN)") (class "Default")
      (node (ref "C30") (pin "+") (pinfunction "+_+") (pintype "passive"))
      (node (ref "C41") (pin "1") (pinfunction "1_1") (pintype "passive"))
      (node (ref "DB1") (pin "+") (pinfunction "+_+") (pintype "bidirectional"))
      (node (ref "IC2") (pin "1") (pinfunction "VIN_1") (pintype "input"))
    )
    (net (code "48") (name "Net-(IC7-O6)") (class "Default")
      (node (ref "IC7") (pin "11") (pinfunction "O6_11") (pintype "open_collector"))
      (node (ref "LED12") (pin "K") (pinfunction "C_K") (pintype "passive"))
    )
    (net (code "49") (name "Net-(LED1-PadA)") (class "Default")
      (node (ref "LED1") (pin "A") (pinfunction "A_A") (pintype "passive"))
      (node (ref "R1") (pin "1") (pinfunction "1_1") (pintype "passive"))
    )
    (net (code "50") (name "Net-(LED2-PadA)") (class "Default")
      (node (ref "LED2") (pin "A") (pinfunction "A_A") (pintype "passive"))
      (node (ref "R2") (pin "2") (pinfunction "2_2") (pintype "passive"))
    )
    (net (code "51") (name "Net-(LED3-PadA)") (class "Default")
      (node (ref "LED3") (pin "A") (pinfunction "A_A") (pintype "passive"))
      (node (ref "R10") (pin "1") (pinfunction "1_1") (pintype "passive"))
    )
    (net (code "52") (name "Net-(LED4-C)") (class "Default")
      (node (ref "LED4") (pin "K") (pinfunction "C_K") (pintype "passive"))
      (node (ref "OK1") (pin "1") (pinfunction "A_1") (pintype "passive"))
    )
    (net (code "53") (name "Net-(LED4-PadA)") (class "Default")
      (node (ref "LED4") (pin "A") (pinfunction "A_A") (pintype "passive"))
      (node (ref "R56") (pin "2") (pinfunction "2_2") (pintype "passive"))
    )
    (net (code "54") (name "Net-(LED5-C)") (class "Default")
      (node (ref "LED5") (pin "K") (pinfunction "C_K") (pintype "passive"))
      (node (ref "OK8") (pin "1") (pinfunction "A_1") (pintype "passive"))
    )
    (net (code "55") (name "Net-(LED5-PadA)") (class "Default")
      (node (ref "LED5") (pin "A") (pinfunction "A_A") (pintype "passive"))
      (node (ref "R54") (pin "2") (pinfunction "2_2") (pintype "passive"))
    )
    (net (code "56") (name "Net-(LED6-C)") (class "Default")
      (node (ref "LED6") (pin "K") (pinfunction "C_K") (pintype "passive"))
      (node (ref "OK2") (pin "1") (pinfunction "A_1") (pintype "passive"))
    )
    (net (code "57") (name "Net-(LED6-PadA)") (class "Default")
      (node (ref "LED6") (pin "A") (pinfunction "A_A") (pintype "passive"))
      (node (ref "R58") (pin "2") (pinfunction "2_2") (pintype "passive"))
    )
    (net (code "58") (name "Net-(LED7-PadA)") (class "Default")
      (node (ref "LED7") (pin "A") (pinfunction "A_A") (pintype "passive"))
      (node (ref "R12") (pin "1") (pinfunction "1_1") (pintype "passive"))
    )
    (net (code "59") (name "Net-(LED8-PadA)") (class "Default")
      (node (ref "LED8") (pin "A") (pinfunction "A_A") (pintype "passive"))
      (node (ref "R9") (pin "1") (pinfunction "1_1") (pintype "passive"))
    )
    (net (code "60") (name "Net-(LED9-PadA)") (class "Default")
      (node (ref "LED9") (pin "A") (pinfunction "A_A") (pintype "passive"))
      (node (ref "R13") (pin "1") (pinfunction "1_1") (pintype "passive"))
    )
    (net (code "61") (name "Net-(LED10-PadA)") (class "Default")
      (node (ref "LED10") (pin "A") (pinfunction "A_A") (pintype "passive"))
      (node (ref "R8") (pin "1") (pinfunction "1_1") (pintype "passive"))
    )
    (net (code "62") (name "Net-(LED11-C)") (class "Default")
      (node (ref "LED11") (pin "K") (pinfunction "C_K") (pintype "passive"))
      (node (ref "OK3") (pin "1") (pinfunction "A_1") (pintype "passive"))
    )
    (net (code "63") (name "Net-(LED11-PadA)") (class "Default")
      (node (ref "LED11") (pin "A") (pinfunction "A_A") (pintype "passive"))
      (node (ref "R60") (pin "2") (pinfunction "2_2") (pintype "passive"))
    )
    (net (code "64") (name "Net-(LED12-PadA)") (class "Default")
      (node (ref "LED12") (pin "A") (pinfunction "A_A") (pintype "passive"))
      (node (ref "R14") (pin "2") (pinfunction "2_2") (pintype "passive"))
    )
    (net (code "65") (name "Net-(LED13-C)") (class "Default")
      (node (ref "LED13") (pin "K") (pinfunction "C_K") (pintype "passive"))
      (node (ref "OK4") (pin "1") (pinfunction "A_1") (pintype "passive"))
    )
    (net (code "66") (name "Net-(LED13-PadA)") (class "Default")
      (node (ref "LED13") (pin "A") (pinfunction "A_A") (pintype "passive"))
      (node (ref "R5") (pin "2") (pinfunction "2_2") (pintype "passive"))
    )
    (net (code "67") (name "Net-(Q8-PadB)") (class "Default")
      (node (ref "Q8") (pin "B") (pinfunction "B_B") (pintype "passive"))
      (node (ref "R79") (pin "2") (pinfunction "2_2") (pintype "passive"))
      (node (ref "R82") (pin "1") (pinfunction "1_1") (pintype "passive"))
    )
    (net (code "68") (name "Net-(Q9-PadB)") (class "Default")
      (node (ref "Q9") (pin "B") (pinfunction "B_B") (pintype "passive"))
      (node (ref "R80") (pin "2") (pinfunction "2_2") (pintype "passive"))
      (node (ref "R81") (pin "1") (pinfunction "1_1") (pintype "passive"))
    )
    (net (code "69") (name "Net-(X2A-KL)") (class "Default")
      (node (ref "DB1") (pin "P$1") (pinfunction "~_P$1") (pintype "bidirectional"))
      (node (ref "MOV") (pin "1") (pinfunction "1_1") (pintype "bidirectional"))
      (node (ref "X2") (pin "1") (pinfunction "KL_1") (pintype "passive"))
    )
    (net (code "70") (name "Net-(X2B-KL)") (class "Default")
      (node (ref "FUSE") (pin "IN") (pinfunction "IN_IN") (pintype "bidirectional"))
      (node (ref "X2") (pin "2") (pinfunction "KL_2") (pintype "passive"))
    )
    (net (code "71") (name "OSC1") (class "Default")
      (node (ref "C31") (pin "2") (pinfunction "2_2") (pintype "passive"))
      (node (ref "IC1") (pin "30") (pinfunction "OSC1/CLKIN_30") (pintype "input"))
      (node (ref "Q3") (pin "1") (pinfunction "1_1") (pintype "passive"))
    )
    (net (code "72") (name "OSC2") (class "Default")
      (node (ref "C32") (pin "2") (pinfunction "2_2") (pintype "passive"))
      (node (ref "IC1") (pin "31") (pinfunction "OSC2/CLKOUT_31") (pintype "output"))
      (node (ref "Q3") (pin "2") (pinfunction "2_2") (pintype "passive"))
    )
    (net (code "73") (name "PGC") (class "Default")
      (node (ref "IC1") (pin "16") (pinfunction "PGC/RB6_16") (pintype "bidirectional"))
      (node (ref "ICSP") (pin "5") (pinfunction "5_5") (pintype "passive"))
    )
    (net (code "74") (name "PGD") (class "Default")
      (node (ref "IC1") (pin "17") (pinfunction "PGD/RB7_17") (pintype "bidirectional"))
      (node (ref "ICSP") (pin "4") (pinfunction "4_4") (pintype "passive"))
    )
    (net (code "75") (name "RELOAD") (class "Default")
      (node (ref "ETH2") (pin "P$6") (pinfunction "RELOAD(CFG)_P$6") (pintype "bidirectional"))
      (node (ref "SV2") (pin "4") (pinfunction "4_4") (pintype "passive"))
    )
    (net (code "76") (name "RELOAD_UP") (class "Default")
      (node (ref "Q8") (pin "C") (pinfunction "C_C") (pintype "passive"))
      (node (ref "SV1") (pin "2") (pinfunction "2_2") (pintype "passive"))
    )
    (net (code "77") (name "RELOAD_UP_IO") (class "Default")
      (node (ref "IC1") (pin "37") (pinfunction "RC3/SCK_37") (pintype "bidirectional"))
      (node (ref "R79") (pin "1") (pinfunction "1_1") (pintype "passive"))
    )
    (net (code "78") (name "RI1") (class "Default")
      (node (ref "IC1") (pin "43") (pinfunction "SDO/RC5_43") (pintype "bidirectional"))
      (node (ref "IC7") (pin "1") (pinfunction "I1_1") (pintype "input"))
    )
    (net (code "79") (name "RI2") (class "Default")
      (node (ref "IC1") (pin "42") (pinfunction "SDI/RC4_42") (pintype "bidirectional"))
      (node (ref "IC7") (pin "2") (pinfunction "I2_2") (pintype "input"))
    )
    (net (code "80") (name "RI3") (class "Default")
      (node (ref "IC1") (pin "41") (pinfunction "RD3/PSP3_41") (pintype "bidirectional"))
      (node (ref "IC7") (pin "3") (pinfunction "I3_3") (pintype "input"))
    )
    (net (code "81") (name "RI4") (class "Default")
      (node (ref "IC1") (pin "40") (pinfunction "RD2/PSP2_40") (pintype "bidirectional"))
      (node (ref "IC7") (pin "4") (pinfunction "I4_4") (pintype "input"))
    )
    (net (code "82") (name "RI5") (class "Default")
      (node (ref "IC1") (pin "39") (pinfunction "RD1/PSP1_39") (pintype "bidirectional"))
      (node (ref "IC7") (pin "5") (pinfunction "I5_5") (pintype "input"))
    )
    (net (code "83") (name "RO1") (class "Default")
      (node (ref "D3") (pin "A") (pinfunction "A_A") (pintype "passive"))
      (node (ref "RLY1") (pin "2") (pinfunction "2_2") (pintype "bidirectional"))
      (node (ref "SV2") (pin "15") (pinfunction "15_15") (pintype "passive"))
    )
    (net (code "84") (name "RO1_UP") (class "Default")
      (node (ref "IC7") (pin "16") (pinfunction "O1_16") (pintype "open_collector"))
      (node (ref "LED10") (pin "K") (pinfunction "C_K") (pintype "passive"))
      (node (ref "SV1") (pin "15") (pinfunction "15_15") (pintype "passive"))
    )
    (net (code "85") (name "RO2") (class "Default")
      (node (ref "D4") (pin "A") (pinfunction "A_A") (pintype "passive"))
      (node (ref "RLY2") (pin "2") (pinfunction "2_2") (pintype "bidirectional"))
      (node (ref "SV2") (pin "13") (pinfunction "13_13") (pintype "passive"))
    )
    (net (code "86") (name "RO2_UP") (class "Default")
      (node (ref "IC7") (pin "15") (pinfunction "O2_15") (pintype "open_collector"))
      (node (ref "LED8") (pin "K") (pinfunction "C_K") (pintype "passive"))
      (node (ref "SV1") (pin "13") (pinfunction "13_13") (pintype "passive"))
    )
    (net (code "87") (name "RO3") (class "Default")
      (node (ref "D1") (pin "A") (pinfunction "A_A") (pintype "passive"))
      (node (ref "RLY3") (pin "2") (pinfunction "2_2") (pintype "bidirectional"))
      (node (ref "SV2") (pin "11") (pinfunction "11_11") (pintype "passive"))
    )
    (net (code "88") (name "RO3_UP") (class "Default")
      (node (ref "IC7") (pin "14") (pinfunction "O3_14") (pintype "open_collector"))
      (node (ref "LED3") (pin "K") (pinfunction "C_K") (pintype "passive"))
      (node (ref "SV1") (pin "11") (pinfunction "11_11") (pintype "passive"))
    )
    (net (code "89") (name "RO4") (class "Default")
      (node (ref "D2") (pin "A") (pinfunction "A_A") (pintype "passive"))
      (node (ref "RLY4") (pin "2") (pinfunction "2_2") (pintype "bidirectional"))
      (node (ref "SV2") (pin "9") (pinfunction "9_9") (pintype "passive"))
    )
    (net (code "90") (name "RO4_UP") (class "Default")
      (node (ref "IC7") (pin "13") (pinfunction "O4_13") (pintype "open_collector"))
      (node (ref "LED7") (pin "K") (pinfunction "C_K") (pintype "passive"))
      (node (ref "SV1") (pin "9") (pinfunction "9_9") (pintype "passive"))
    )
    (net (code "91") (name "RO5") (class "Default")
      (node (ref "D6") (pin "A") (pinfunction "A_A") (pintype "passive"))
      (node (ref "RLY5") (pin "2") (pinfunction "2_2") (pintype "bidirectional"))
      (node (ref "SV2") (pin "7") (pinfunction "7_7") (pintype "passive"))
    )
    (net (code "92") (name "RO5_UP") (class "Default")
      (node (ref "IC7") (pin "12") (pinfunction "O5_12") (pintype "open_collector"))
      (node (ref "LED9") (pin "K") (pinfunction "C_K") (pintype "passive"))
      (node (ref "SV1") (pin "7") (pinfunction "7_7") (pintype "passive"))
    )
    (net (code "93") (name "RST") (class "Default")
      (node (ref "ETH2") (pin "P$4") (pinfunction "RST_P$4") (pintype "bidirectional"))
      (node (ref "SV2") (pin "2") (pinfunction "2_2") (pintype "passive"))
    )
    (net (code "94") (name "RST_UP") (class "Default")
      (node (ref "Q9") (pin "C") (pinfunction "C_C") (pintype "passive"))
      (node (ref "SV1") (pin "4") (pinfunction "4_4") (pintype "passive"))
    )
    (net (code "95") (name "RST_UP_IO") (class "Default")
      (node (ref "IC1") (pin "36") (pinfunction "RC2/CCP1_36") (pintype "bidirectional"))
      (node (ref "R80") (pin "1") (pinfunction "1_1") (pintype "passive"))
    )
    (net (code "96") (name "RX") (class "Default")
      (node (ref "IC1") (pin "1") (pinfunction "RX/RC7_1") (pintype "bidirectional"))
      (node (ref "R3") (pin "1") (pinfunction "1_1") (pintype "passive"))
      (node (ref "SV1") (pin "3") (pinfunction "3_3") (pintype "passive"))
    )
    (net (code "97") (name "RX_ETH") (class "Default")
      (node (ref "ETH2") (pin "P$8") (pinfunction "RXD_P$8") (pintype "bidirectional"))
      (node (ref "SV2") (pin "1") (pinfunction "1_1") (pintype "passive"))
    )
    (net (code "98") (name "STATUS") (class "Default")
      (node (ref "IC1") (pin "38") (pinfunction "RD0/PSP0_38") (pintype "bidirectional"))
      (node (ref "IC7") (pin "6") (pinfunction "I6_6") (pintype "input"))
    )
    (net (code "99") (name "TX") (class "Default")
      (node (ref "IC1") (pin "44") (pinfunction "TX/RC6_44") (pintype "bidirectional"))
      (node (ref "R6") (pin "1") (pinfunction "1_1") (pintype "passive"))
      (node (ref "SV1") (pin "1") (pinfunction "1_1") (pintype "passive"))
    )
    (net (code "100") (name "TX_ETH") (class "Default")
      (node (ref "ETH2") (pin "P$9") (pinfunction "TXD_P$9") (pintype "bidirectional"))
      (node (ref "SV2") (pin "3") (pinfunction "3_3") (pintype "passive"))
    )
    (net (code "101") (name "VSS") (class "Default")
      (node (ref "OK1") (pin "2") (pinfunction "C_2") (pintype "passive"))
      (node (ref "OK2") (pin "2") (pinfunction "C_2") (pintype "passive"))
      (node (ref "OK3") (pin "2") (pinfunction "C_2") (pintype "passive"))
      (node (ref "OK4") (pin "2") (pinfunction "C_2") (pintype "passive"))
      (node (ref "OK8") (pin "2") (pinfunction "C_2") (pintype "passive"))
      (node (ref "SV1") (pin "10") (pinfunction "10_10") (pintype "passive"))
    )
    (net (code "102") (name "unconnected-(ETH2-LINK-PadP$3)") (class "Default")
      (node (ref "ETH2") (pin "P$3") (pinfunction "LINK_P$3") (pintype "bidirectional"))
    )
    (net (code "103") (name "unconnected-(ETH2-NC1-PadP$1)") (class "Default")
      (node (ref "ETH2") (pin "P$1") (pinfunction "NC1_P$1") (pintype "bidirectional"))
    )
    (net (code "104") (name "unconnected-(ETH2-NC2-PadP$2)") (class "Default")
      (node (ref "ETH2") (pin "P$2") (pinfunction "NC2_P$2") (pintype "bidirectional"))
    )
    (net (code "105") (name "unconnected-(ETH2-RTS-PadP$5)") (class "Default")
      (node (ref "ETH2") (pin "P$5") (pinfunction "RTS_P$5") (pintype "bidirectional"))
    )
    (net (code "106") (name "unconnected-(IC1-PGM{slash}RB3-Pad11)") (class "Default")
      (node (ref "IC1") (pin "11") (pinfunction "PGM/RB3_11") (pintype "bidirectional"))
    )
    (net (code "107") (name "unconnected-(IC1-PSP4{slash}RD4-Pad2)") (class "Default")
      (node (ref "IC1") (pin "2") (pinfunction "PSP4/RD4_2") (pintype "bidirectional"))
    )
    (net (code "108") (name "unconnected-(IC1-PSP5{slash}RD5-Pad3)") (class "Default")
      (node (ref "IC1") (pin "3") (pinfunction "PSP5/RD5_3") (pintype "bidirectional"))
    )
    (net (code "109") (name "unconnected-(IC1-PSP6{slash}RD6-Pad4)") (class "Default")
      (node (ref "IC1") (pin "4") (pinfunction "PSP6/RD6_4") (pintype "bidirectional"))
    )
    (net (code "110") (name "unconnected-(IC1-PSP7{slash}RD7-Pad5)") (class "Default")
      (node (ref "IC1") (pin "5") (pinfunction "PSP7/RD7_5") (pintype "bidirectional"))
    )
    (net (code "111") (name "unconnected-(IC1-RA0{slash}AN0-Pad19)") (class "Default")
      (node (ref "IC1") (pin "19") (pinfunction "RA0/AN0_19") (pintype "bidirectional"))
    )
    (net (code "112") (name "unconnected-(IC1-RA1{slash}AN1-Pad20)") (class "Default")
      (node (ref "IC1") (pin "20") (pinfunction "RA1/AN1_20") (pintype "bidirectional"))
    )
    (net (code "113") (name "unconnected-(IC1-RA2{slash}AN2-Pad21)") (class "Default")
      (node (ref "IC1") (pin "21") (pinfunction "RA2/AN2_21") (pintype "bidirectional"))
    )
    (net (code "114") (name "unconnected-(IC1-RA3{slash}AN3-Pad22)") (class "Default")
      (node (ref "IC1") (pin "22") (pinfunction "RA3/AN3_22") (pintype "bidirectional"))
    )
    (net (code "115") (name "unconnected-(IC1-RA4{slash}T0CKI-Pad23)") (class "Default")
      (node (ref "IC1") (pin "23") (pinfunction "RA4/T0CKI_23") (pintype "bidirectional"))
    )
    (net (code "116") (name "unconnected-(IC1-RA5{slash}AN4-Pad24)") (class "Default")
      (node (ref "IC1") (pin "24") (pinfunction "RA5/AN4_24") (pintype "bidirectional"))
    )
    (net (code "117") (name "unconnected-(IC1-RC0{slash}T1OSO-Pad32)") (class "Default")
      (node (ref "IC1") (pin "32") (pinfunction "RC0/T1OSO_32") (pintype "bidirectional"))
    )
    (net (code "118") (name "unconnected-(IC1-RC1{slash}T1OSI-Pad35)") (class "Default")
      (node (ref "IC1") (pin "35") (pinfunction "RC1/T1OSI_35") (pintype "bidirectional"))
    )
    (net (code "119") (name "unconnected-(IC1-RE0{slash}~{RD{slash}AN5}-Pad25)") (class "Default")
      (node (ref "IC1") (pin "25") (pinfunction "RE0/~{RD/AN5}_25") (pintype "bidirectional"))
    )
    (net (code "120") (name "unconnected-(IC1-RE1{slash}~{WR{slash}AN6}-Pad26)") (class "Default")
      (node (ref "IC1") (pin "26") (pinfunction "RE1/~{WR/AN6}_26") (pintype "bidirectional"))
    )
    (net (code "121") (name "unconnected-(IC1-RE2{slash}~{CS{slash}AN7}-Pad27)") (class "Default")
      (node (ref "IC1") (pin "27") (pinfunction "RE2/~{CS/AN7}_27") (pintype "bidirectional"))
    )
    (net (code "122") (name "unconnected-(IC7-I7-Pad7)") (class "Default")
      (node (ref "IC7") (pin "7") (pinfunction "I7_7") (pintype "input"))
    )
    (net (code "123") (name "unconnected-(IC7-O7-Pad10)") (class "Default")
      (node (ref "IC7") (pin "10") (pinfunction "O7_10") (pintype "open_collector"))
    )
  )
)
